# MCU_IMU.net
KiCad netlist of a schematic drawn in Altium Designer
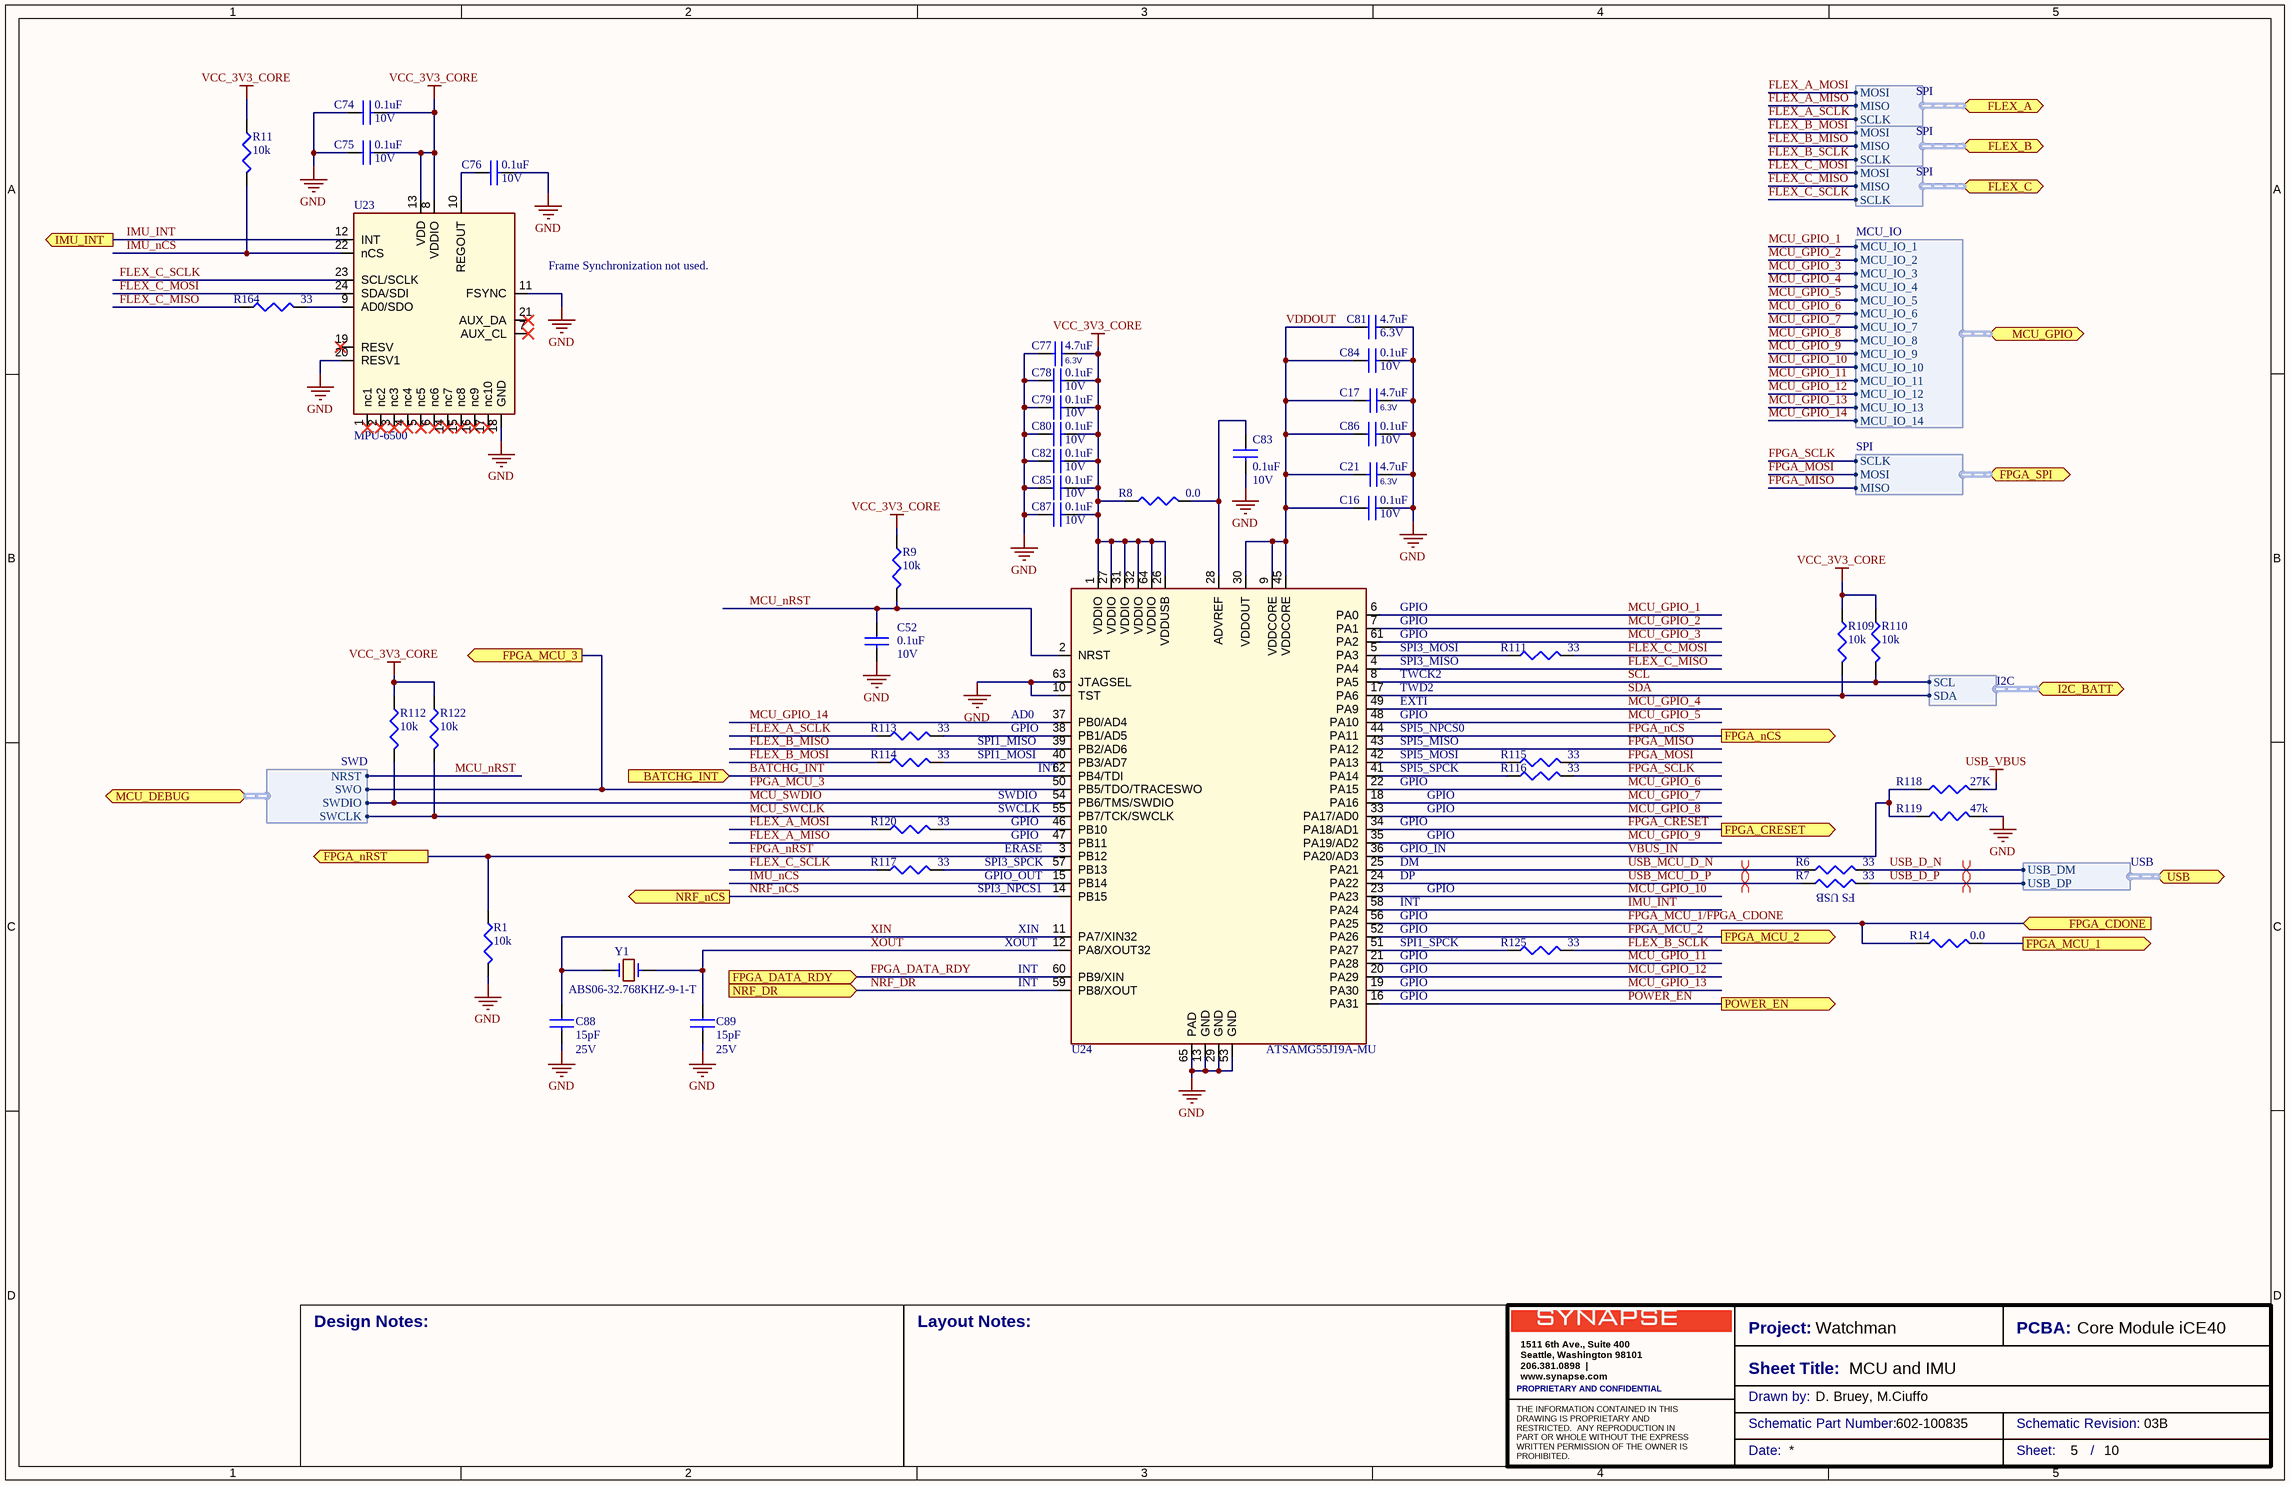
[diagram p0: MCU_IMU.SchDoc]

(export (version "E")
  (design (tool "Eeschema 10.0.6"))
  (components
    (comp (ref "C16")
      (value "0.1uF")
      (footprint "0201-IPCsm_33")
      (description "CAP CER 0.1UF 10V 10% X5R 0201")
      (fields
        (field (name "VOLTAGE") "10V")
        (field (name "MFG") "Samsung Electro-Mechanics America, Inc")
        (field (name "TOLERANCE") "10%")
      )
      (libsource (lib "SynapseLibrary") (part "CAP"))
    )
    (comp (ref "C17")
      (value "4.7uF")
      (footprint "0402-IPCsm_55")
      (description "CAP CER 4.7UF 6.3V 20% X5R 0402")
      (fields (field (name "VOLTAGE") "6.3V") (field (name "MFG") "MURATA") (field (name "TOLERANCE") "20%"))
      (libsource (lib "SynapseLibrary") (part "CAP"))
    )
    (comp (ref "C21")
      (value "4.7uF")
      (footprint "0402-IPCsm_55")
      (description "CAP CER 4.7UF 6.3V 20% X5R 0402")
      (fields (field (name "VOLTAGE") "6.3V") (field (name "MFG") "MURATA") (field (name "TOLERANCE") "20%"))
      (libsource (lib "SynapseLibrary") (part "CAP"))
    )
    (comp (ref "C52")
      (value "0.1uF")
      (footprint "0201-IPCsm_33")
      (description "CAP CER 0.1UF 10V 10% X5R 0201")
      (fields
        (field (name "VOLTAGE") "10V")
        (field (name "MFG") "Samsung Electro-Mechanics America, Inc")
        (field (name "TOLERANCE") "10%")
      )
      (libsource (lib "SynapseLibrary") (part "CAP"))
    )
    (comp (ref "C74")
      (value "0.1uF")
      (footprint "0201-IPCsm_33")
      (description "CAP CER 0.1UF 10V 10% X5R 0201")
      (fields
        (field (name "VOLTAGE") "10V")
        (field (name "MFG") "Samsung Electro-Mechanics America, Inc")
        (field (name "TOLERANCE") "10%")
      )
      (libsource (lib "SynapseLibrary") (part "CAP"))
    )
    (comp (ref "C75")
      (value "0.1uF")
      (footprint "0201-IPCsm_33")
      (description "CAP CER 0.1UF 10V 10% X5R 0201")
      (fields
        (field (name "VOLTAGE") "10V")
        (field (name "MFG") "Samsung Electro-Mechanics America, Inc")
        (field (name "TOLERANCE") "10%")
      )
      (libsource (lib "SynapseLibrary") (part "CAP"))
    )
    (comp (ref "C76")
      (value "0.1uF")
      (footprint "0201-IPCsm_33")
      (description "CAP CER 0.1UF 10V 10% X5R 0201")
      (fields
        (field (name "VOLTAGE") "10V")
        (field (name "MFG") "Samsung Electro-Mechanics America, Inc")
        (field (name "TOLERANCE") "10%")
      )
      (libsource (lib "SynapseLibrary") (part "CAP"))
    )
    (comp (ref "C77")
      (value "4.7uF")
      (footprint "0402-IPCsm_55")
      (description "CAP CER 4.7UF 6.3V 20% X5R 0402")
      (fields (field (name "VOLTAGE") "6.3V") (field (name "MFG") "MURATA") (field (name "TOLERANCE") "20%"))
      (libsource (lib "SynapseLibrary") (part "CAP"))
    )
    (comp (ref "C78")
      (value "0.1uF")
      (footprint "0201-IPCsm_33")
      (description "CAP CER 0.1UF 10V 10% X5R 0201")
      (fields
        (field (name "VOLTAGE") "10V")
        (field (name "MFG") "Samsung Electro-Mechanics America, Inc")
        (field (name "TOLERANCE") "10%")
      )
      (libsource (lib "SynapseLibrary") (part "CAP"))
    )
    (comp (ref "C79")
      (value "0.1uF")
      (footprint "0201-IPCsm_33")
      (description "CAP CER 0.1UF 10V 10% X5R 0201")
      (fields
        (field (name "VOLTAGE") "10V")
        (field (name "MFG") "Samsung Electro-Mechanics America, Inc")
        (field (name "TOLERANCE") "10%")
      )
      (libsource (lib "SynapseLibrary") (part "CAP"))
    )
    (comp (ref "C80")
      (value "0.1uF")
      (footprint "0201-IPCsm_33")
      (description "CAP CER 0.1UF 10V 10% X5R 0201")
      (fields
        (field (name "VOLTAGE") "10V")
        (field (name "MFG") "Samsung Electro-Mechanics America, Inc")
        (field (name "TOLERANCE") "10%")
      )
      (libsource (lib "SynapseLibrary") (part "CAP"))
    )
    (comp (ref "C81")
      (value "4.7uF")
      (footprint "0402-IPCsm_55")
      (description "CAP CER 4.7UF 6.3V 20% X5R 0402")
      (fields (field (name "VOLTAGE") "6.3V") (field (name "MFG") "MURATA") (field (name "TOLERANCE") "20%"))
      (libsource (lib "SynapseLibrary") (part "CAP"))
    )
    (comp (ref "C82")
      (value "0.1uF")
      (footprint "0201-IPCsm_33")
      (description "CAP CER 0.1UF 10V 10% X5R 0201")
      (fields
        (field (name "VOLTAGE") "10V")
        (field (name "MFG") "Samsung Electro-Mechanics America, Inc")
        (field (name "TOLERANCE") "10%")
      )
      (libsource (lib "SynapseLibrary") (part "CAP"))
    )
    (comp (ref "C83")
      (value "0.1uF")
      (footprint "0201-IPCsm_33")
      (description "CAP CER 0.1UF 10V 10% X5R 0201")
      (fields
        (field (name "VOLTAGE") "10V")
        (field (name "MFG") "Samsung Electro-Mechanics America, Inc")
        (field (name "TOLERANCE") "10%")
      )
      (libsource (lib "SynapseLibrary") (part "CAP"))
    )
    (comp (ref "C84")
      (value "0.1uF")
      (footprint "0201-IPCsm_33")
      (description "CAP CER 0.1UF 10V 10% X5R 0201")
      (fields
        (field (name "VOLTAGE") "10V")
        (field (name "MFG") "Samsung Electro-Mechanics America, Inc")
        (field (name "TOLERANCE") "10%")
      )
      (libsource (lib "SynapseLibrary") (part "CAP"))
    )
    (comp (ref "C85")
      (value "0.1uF")
      (footprint "0201-IPCsm_33")
      (description "CAP CER 0.1UF 10V 10% X5R 0201")
      (fields
        (field (name "VOLTAGE") "10V")
        (field (name "MFG") "Samsung Electro-Mechanics America, Inc")
        (field (name "TOLERANCE") "10%")
      )
      (libsource (lib "SynapseLibrary") (part "CAP"))
    )
    (comp (ref "C86")
      (value "0.1uF")
      (footprint "0201-IPCsm_33")
      (description "CAP CER 0.1UF 10V 10% X5R 0201")
      (fields
        (field (name "VOLTAGE") "10V")
        (field (name "MFG") "Samsung Electro-Mechanics America, Inc")
        (field (name "TOLERANCE") "10%")
      )
      (libsource (lib "SynapseLibrary") (part "CAP"))
    )
    (comp (ref "C87")
      (value "0.1uF")
      (footprint "0201-IPCsm_33")
      (description "CAP CER 0.1UF 10V 10% X5R 0201")
      (fields
        (field (name "VOLTAGE") "10V")
        (field (name "MFG") "Samsung Electro-Mechanics America, Inc")
        (field (name "TOLERANCE") "10%")
      )
      (libsource (lib "SynapseLibrary") (part "CAP"))
    )
    (comp (ref "C88")
      (value "15pF")
      (footprint "0201-IPCsm_33")
      (description "CAP CER 15PF 25V C0G 0201")
      (fields (field (name "VOLTAGE") "25V") (field (name "MFG") "Murata") (field (name "TOLERANCE") "5%"))
      (libsource (lib "SynapseLibrary") (part "CAP"))
    )
    (comp (ref "C89")
      (value "15pF")
      (footprint "0201-IPCsm_33")
      (description "CAP CER 15PF 25V C0G 0201")
      (fields (field (name "VOLTAGE") "25V") (field (name "MFG") "Murata") (field (name "TOLERANCE") "5%"))
      (libsource (lib "SynapseLibrary") (part "CAP"))
    )
    (comp (ref "R1")
      (value "10k")
      (footprint "0201-IPCsm_26")
      (description "RES 10K OHM 1/20W 1% 0201 SMD")
      (fields (field (name "TOLERANCE") "1.00%") (field (name "VOLTAGE") "50V"))
      (libsource (lib "SynapseLibrary") (part "RES"))
    )
    (comp (ref "R6")
      (value "33")
      (footprint "0201-IPCsm_26")
      (description "RES 33 OHM 1/20W 1% 0201 SMD")
      (fields (field (name "TOLERANCE") "1.00%") (field (name "VOLTAGE") "50V"))
      (libsource (lib "SynapseLibrary") (part "RES"))
    )
    (comp (ref "R7")
      (value "33")
      (footprint "0201-IPCsm_26")
      (description "RES 33 OHM 1/20W 1% 0201 SMD")
      (fields (field (name "TOLERANCE") "1.00%") (field (name "VOLTAGE") "50V"))
      (libsource (lib "SynapseLibrary") (part "RES"))
    )
    (comp (ref "R8")
      (value "0.0")
      (footprint "0201-IPCsm_26")
      (description "RES SMD 0.0OHM JUMPER 1/20W 0201")
      (fields (field (name "MFG") "Panasonic") (field (name "POWER") "0.05W"))
      (libsource (lib "SynapseLibrary") (part "RES"))
    )
    (comp (ref "R9")
      (value "10k")
      (footprint "0201-IPCsm_26")
      (description "RES 10K OHM 1/20W 1% 0201 SMD")
      (fields (field (name "TOLERANCE") "1.00%") (field (name "VOLTAGE") "50V"))
      (libsource (lib "SynapseLibrary") (part "RES"))
    )
    (comp (ref "R11")
      (value "10k")
      (footprint "0201-IPCsm_26")
      (description "RES 10K OHM 1/20W 1% 0201 SMD")
      (fields (field (name "TOLERANCE") "1.00%") (field (name "VOLTAGE") "50V"))
      (libsource (lib "SynapseLibrary") (part "RES"))
    )
    (comp (ref "R14")
      (value "0.0")
      (footprint "0201-IPCsm_26")
      (description "RES SMD 0.0OHM JUMPER 1/20W 0201")
      (fields (field (name "MFG") "Panasonic") (field (name "POWER") "0.05W"))
      (libsource (lib "SynapseLibrary") (part "RES"))
    )
    (comp (ref "R109")
      (value "10k")
      (footprint "0201-IPCsm_26")
      (description "RES 10K OHM 1/20W 1% 0201 SMD")
      (fields (field (name "TOLERANCE") "1.00%") (field (name "VOLTAGE") "50V"))
      (libsource (lib "SynapseLibrary") (part "RES"))
    )
    (comp (ref "R110")
      (value "10k")
      (footprint "0201-IPCsm_26")
      (description "RES 10K OHM 1/20W 1% 0201 SMD")
      (fields (field (name "TOLERANCE") "1.00%") (field (name "VOLTAGE") "50V"))
      (libsource (lib "SynapseLibrary") (part "RES"))
    )
    (comp (ref "R111")
      (value "33")
      (footprint "0201-IPCsm_26")
      (description "RES 33 OHM 1/20W 1% 0201 SMD")
      (fields (field (name "TOLERANCE") "1.00%") (field (name "VOLTAGE") "50V"))
      (libsource (lib "SynapseLibrary") (part "RES"))
    )
    (comp (ref "R112")
      (value "10k")
      (footprint "0201-IPCsm_26")
      (description "RES 10K OHM 1/20W 1% 0201 SMD")
      (fields (field (name "TOLERANCE") "1.00%") (field (name "VOLTAGE") "50V"))
      (libsource (lib "SynapseLibrary") (part "RES"))
    )
    (comp (ref "R113")
      (value "33")
      (footprint "0201-IPCsm_26")
      (description "RES 33 OHM 1/20W 1% 0201 SMD")
      (fields (field (name "TOLERANCE") "1.00%") (field (name "VOLTAGE") "50V"))
      (libsource (lib "SynapseLibrary") (part "RES"))
    )
    (comp (ref "R114")
      (value "33")
      (footprint "0201-IPCsm_26")
      (description "RES 33 OHM 1/20W 1% 0201 SMD")
      (fields (field (name "TOLERANCE") "1.00%") (field (name "VOLTAGE") "50V"))
      (libsource (lib "SynapseLibrary") (part "RES"))
    )
    (comp (ref "R115")
      (value "33")
      (footprint "0201-IPCsm_26")
      (description "RES 33 OHM 1/20W 1% 0201 SMD")
      (fields (field (name "TOLERANCE") "1.00%") (field (name "VOLTAGE") "50V"))
      (libsource (lib "SynapseLibrary") (part "RES"))
    )
    (comp (ref "R116")
      (value "33")
      (footprint "0201-IPCsm_26")
      (description "RES 33 OHM 1/20W 1% 0201 SMD")
      (fields (field (name "TOLERANCE") "1.00%") (field (name "VOLTAGE") "50V"))
      (libsource (lib "SynapseLibrary") (part "RES"))
    )
    (comp (ref "R117")
      (value "33")
      (footprint "0201-IPCsm_26")
      (description "RES 33 OHM 1/20W 1% 0201 SMD")
      (fields (field (name "TOLERANCE") "1.00%") (field (name "VOLTAGE") "50V"))
      (libsource (lib "SynapseLibrary") (part "RES"))
    )
    (comp (ref "R118")
      (value "27K")
      (footprint "0201-IPCsm_26")
      (description "RES 27K OHM 1/20W 1% 0201 SMD")
      (fields (field (name "TOLERANCE") "1.00%") (field (name "VOLTAGE") "15V"))
      (libsource (lib "SynapseLibrary") (part "RES"))
    )
    (comp (ref "R119")
      (value "47k")
      (footprint "0201-IPCsm_26")
      (description "RES 47K OHM 1/20W 5% 0201 SMD")
      (fields (field (name "TOLERANCE") "5.00%") (field (name "VOLTAGE") "50V"))
      (libsource (lib "SynapseLibrary") (part "RES"))
    )
    (comp (ref "R120")
      (value "33")
      (footprint "0201-IPCsm_26")
      (description "RES 33 OHM 1/20W 1% 0201 SMD")
      (fields (field (name "TOLERANCE") "1.00%") (field (name "VOLTAGE") "50V"))
      (libsource (lib "SynapseLibrary") (part "RES"))
    )
    (comp (ref "R122")
      (value "10k")
      (footprint "0201-IPCsm_26")
      (description "RES 10K OHM 1/20W 1% 0201 SMD")
      (fields (field (name "TOLERANCE") "1.00%") (field (name "VOLTAGE") "50V"))
      (libsource (lib "SynapseLibrary") (part "RES"))
    )
    (comp (ref "R125")
      (value "33")
      (footprint "0201-IPCsm_26")
      (description "RES 33 OHM 1/20W 1% 0201 SMD")
      (fields (field (name "TOLERANCE") "1.00%") (field (name "VOLTAGE") "50V"))
      (libsource (lib "SynapseLibrary") (part "RES"))
    )
    (comp (ref "R164")
      (value "33")
      (footprint "0201-IPCsm_26")
      (description "RES 33 OHM 1/20W 1% 0201 SMD")
      (fields (field (name "TOLERANCE") "1.00%") (field (name "VOLTAGE") "50V"))
      (libsource (lib "SynapseLibrary") (part "RES"))
    )
    (comp (ref "U23")
      (value "MPU-6500")
      (footprint "QFN24_mpu-6500_3x3")
      (description "6-axis Gyroscope/Accelerometer")
      (fields (field (name "MFG") "InvenSense"))
      (libsource (lib "SynapseLibrary") (part "MPU-6500a"))
    )
    (comp (ref "U24")
      (value "ATSAMG55J19A-MU")
      (footprint "qfn64_atsamg55j19a_no_vias")
      (description "IC MCU 32BIT 512KB FLASH 64VQFN")
      (fields (field (name "MFG") "Atmel") (field (name "VOLTAGE") "1.62V~3.6V"))
      (libsource (lib "SynapseLibrary") (part "ATSAMG55J19A-MU"))
    )
    (comp (ref "Y1")
      (value "ABS06-32.768KHZ-9-1-T")
      (footprint "xtal_abs06")
      (description "CRYSTAL 32.768 KHZ 9PF SMD")
      (fields (field (name "MFG") "Abracon") (field (name "TOLERANCE") "+/- 10ppm"))
      (libsource (lib "SynapseLibrary") (part "XTAL_32K"))
    )
  )
  (nets
    (net (code "6") (name "/BATCHG_INT") (class "Default")
      (node (ref "U24") (pin "62") (pinfunction "PB4/TDI_62") (pintype "passive"))
    )
    (net (code "7") (name "/FLEX_A_MISO") (class "Default")
      (node (ref "U24") (pin "47") (pinfunction "PB11_47") (pintype "passive"))
    )
    (net (code "8") (name "/FLEX_A_MOSI") (class "Default")
      (node (ref "R120") (pin "1") (pinfunction "1_1") (pintype "passive"))
    )
    (net (code "9") (name "/FLEX_A_SCLK") (class "Default")
      (node (ref "R113") (pin "1") (pinfunction "1_1") (pintype "passive"))
    )
    (net (code "10") (name "/FLEX_B_MISO") (class "Default")
      (node (ref "U24") (pin "39") (pinfunction "PB2/AD6_39") (pintype "passive"))
    )
    (net (code "11") (name "/FLEX_B_MOSI") (class "Default")
      (node (ref "R114") (pin "1") (pinfunction "1_1") (pintype "passive"))
    )
    (net (code "12") (name "/FLEX_B_SCLK") (class "Default")
      (node (ref "R125") (pin "2") (pinfunction "2_2") (pintype "passive"))
    )
    (net (code "13") (name "/FLEX_C_MISO") (class "Default")
      (node (ref "R164") (pin "1") (pinfunction "1_1") (pintype "passive"))
      (node (ref "U24") (pin "4") (pinfunction "PA4_4") (pintype "passive"))
    )
    (net (code "14") (name "/FLEX_C_MOSI") (class "Default")
      (node (ref "R111") (pin "2") (pinfunction "2_2") (pintype "passive"))
      (node (ref "U23") (pin "24") (pinfunction "SDA/SDI_24") (pintype "passive"))
    )
    (net (code "15") (name "/FLEX_C_SCLK") (class "Default")
      (node (ref "R117") (pin "1") (pinfunction "1_1") (pintype "passive"))
      (node (ref "U23") (pin "23") (pinfunction "SCL/SCLK_23") (pintype "passive"))
    )
    (net (code "16") (name "/FPGA_CRESET") (class "Default")
      (node (ref "U24") (pin "34") (pinfunction "PA18/AD1_34") (pintype "passive"))
    )
    (net (code "17") (name "/FPGA_DATA_RDY") (class "Default")
      (node (ref "U24") (pin "60") (pinfunction "PB9/XIN_60") (pintype "passive"))
    )
    (net (code "18") (name "/FPGA_MCU_1") (class "Default")
      (node (ref "R14") (pin "1") (pinfunction "1_1") (pintype "passive"))
    )
    (net (code "19") (name "/FPGA_MCU_1{slash}FPGA_CDONE") (class "Default")
      (node (ref "R14") (pin "2") (pinfunction "2_2") (pintype "passive"))
      (node (ref "U24") (pin "56") (pinfunction "PA25_56") (pintype "passive"))
    )
    (net (code "20") (name "/FPGA_MCU_2") (class "Default")
      (node (ref "U24") (pin "52") (pinfunction "PA26_52") (pintype "passive"))
    )
    (net (code "21") (name "/FPGA_MCU_3") (class "Default")
      (node (ref "U24") (pin "50") (pinfunction "PB5/TDO/TRACESWO_50") (pintype "passive"))
    )
    (net (code "22") (name "/FPGA_MISO") (class "Default")
      (node (ref "U24") (pin "43") (pinfunction "PA12_43") (pintype "passive"))
    )
    (net (code "23") (name "/FPGA_MOSI") (class "Default")
      (node (ref "R115") (pin "2") (pinfunction "2_2") (pintype "passive"))
    )
    (net (code "24") (name "/FPGA_SCLK") (class "Default")
      (node (ref "R116") (pin "2") (pinfunction "2_2") (pintype "passive"))
    )
    (net (code "25") (name "/FPGA_nCS") (class "Default")
      (node (ref "U24") (pin "44") (pinfunction "PA11_44") (pintype "passive"))
    )
    (net (code "26") (name "/FPGA_nRST") (class "Default")
      (node (ref "R1") (pin "1") (pinfunction "1_1") (pintype "passive"))
      (node (ref "U24") (pin "3") (pinfunction "PB12_3") (pintype "passive"))
    )
    (net (code "27") (name "/IMU_INT") (class "Default")
      (node (ref "U23") (pin "12") (pinfunction "INT_12") (pintype "passive"))
      (node (ref "U24") (pin "58") (pinfunction "PA24_58") (pintype "passive"))
    )
    (net (code "28") (name "/IMU_nCS") (class "Default")
      (node (ref "R11") (pin "2") (pinfunction "2_2") (pintype "passive"))
      (node (ref "U23") (pin "22") (pinfunction "nCS_22") (pintype "passive"))
      (node (ref "U24") (pin "15") (pinfunction "PB14_15") (pintype "passive"))
    )
    (net (code "29") (name "/MCU_GPIO_1") (class "Default")
      (node (ref "U24") (pin "6") (pinfunction "PA0_6") (pintype "passive"))
    )
    (net (code "30") (name "/MCU_GPIO_2") (class "Default")
      (node (ref "U24") (pin "7") (pinfunction "PA1_7") (pintype "passive"))
    )
    (net (code "31") (name "/MCU_GPIO_3") (class "Default")
      (node (ref "U24") (pin "61") (pinfunction "PA2_61") (pintype "passive"))
    )
    (net (code "32") (name "/MCU_GPIO_4") (class "Default")
      (node (ref "U24") (pin "49") (pinfunction "PA9_49") (pintype "passive"))
    )
    (net (code "33") (name "/MCU_GPIO_5") (class "Default")
      (node (ref "U24") (pin "48") (pinfunction "PA10_48") (pintype "passive"))
    )
    (net (code "34") (name "/MCU_GPIO_6") (class "Default")
      (node (ref "U24") (pin "22") (pinfunction "PA15_22") (pintype "passive"))
    )
    (net (code "35") (name "/MCU_GPIO_7") (class "Default")
      (node (ref "U24") (pin "18") (pinfunction "PA16_18") (pintype "passive"))
    )
    (net (code "36") (name "/MCU_GPIO_8") (class "Default")
      (node (ref "U24") (pin "33") (pinfunction "PA17/AD0_33") (pintype "passive"))
    )
    (net (code "37") (name "/MCU_GPIO_9") (class "Default")
      (node (ref "U24") (pin "35") (pinfunction "PA19/AD2_35") (pintype "passive"))
    )
    (net (code "38") (name "/MCU_GPIO_10") (class "Default")
      (node (ref "U24") (pin "23") (pinfunction "PA23_23") (pintype "passive"))
    )
    (net (code "39") (name "/MCU_GPIO_11") (class "Default")
      (node (ref "U24") (pin "21") (pinfunction "PA28_21") (pintype "passive"))
    )
    (net (code "40") (name "/MCU_GPIO_12") (class "Default")
      (node (ref "U24") (pin "20") (pinfunction "PA29_20") (pintype "passive"))
    )
    (net (code "41") (name "/MCU_GPIO_13") (class "Default")
      (node (ref "U24") (pin "19") (pinfunction "PA30_19") (pintype "passive"))
    )
    (net (code "42") (name "/MCU_GPIO_14") (class "Default")
      (node (ref "U24") (pin "37") (pinfunction "PB0/AD4_37") (pintype "passive"))
    )
    (net (code "43") (name "/MCU_SWCLK") (class "Default")
      (node (ref "R122") (pin "2") (pinfunction "2_2") (pintype "passive"))
      (node (ref "U24") (pin "55") (pinfunction "PB7/TCK/SWCLK_55") (pintype "passive"))
    )
    (net (code "44") (name "/MCU_SWDIO") (class "Default")
      (node (ref "R112") (pin "2") (pinfunction "2_2") (pintype "passive"))
      (node (ref "U24") (pin "54") (pinfunction "PB6/TMS/SWDIO_54") (pintype "passive"))
    )
    (net (code "45") (name "/MCU_nRST") (class "Default")
      (node (ref "C52") (pin "1") (pinfunction "1_1") (pintype "passive"))
      (node (ref "R9") (pin "2") (pinfunction "2_2") (pintype "passive"))
      (node (ref "U24") (pin "2") (pinfunction "NRST_2") (pintype "passive"))
    )
    (net (code "46") (name "/NRF_DR") (class "Default")
      (node (ref "U24") (pin "59") (pinfunction "PB8/XOUT_59") (pintype "passive"))
    )
    (net (code "47") (name "/NRF_nCS") (class "Default")
      (node (ref "U24") (pin "14") (pinfunction "PB15_14") (pintype "passive"))
    )
    (net (code "48") (name "/POWER_EN") (class "Default")
      (node (ref "U24") (pin "16") (pinfunction "PA31_16") (pintype "passive"))
    )
    (net (code "49") (name "/SCL") (class "Default")
      (node (ref "R110") (pin "2") (pinfunction "2_2") (pintype "passive"))
      (node (ref "U24") (pin "8") (pinfunction "PA5_8") (pintype "passive"))
    )
    (net (code "50") (name "/SDA") (class "Default")
      (node (ref "R109") (pin "2") (pinfunction "2_2") (pintype "passive"))
      (node (ref "U24") (pin "17") (pinfunction "PA6_17") (pintype "passive"))
    )
    (net (code "51") (name "/USB_D_N") (class "Default")
      (node (ref "R6") (pin "2") (pinfunction "2_2") (pintype "passive"))
    )
    (net (code "52") (name "/USB_D_P") (class "Default")
      (node (ref "R7") (pin "2") (pinfunction "2_2") (pintype "passive"))
    )
    (net (code "53") (name "/USB_MCU_D_N") (class "Default")
      (node (ref "R6") (pin "1") (pinfunction "1_1") (pintype "passive"))
      (node (ref "U24") (pin "25") (pinfunction "PA21_25") (pintype "passive"))
    )
    (net (code "54") (name "/USB_MCU_D_P") (class "Default")
      (node (ref "R7") (pin "1") (pinfunction "1_1") (pintype "passive"))
      (node (ref "U24") (pin "24") (pinfunction "PA22_24") (pintype "passive"))
    )
    (net (code "55") (name "/VBUS_IN") (class "Default")
      (node (ref "R118") (pin "1") (pinfunction "1_1") (pintype "passive"))
      (node (ref "R119") (pin "1") (pinfunction "1_1") (pintype "passive"))
      (node (ref "U24") (pin "36") (pinfunction "PA20/AD3_36") (pintype "passive"))
    )
    (net (code "56") (name "/VDDOUT") (class "Default")
      (node (ref "C16") (pin "1") (pinfunction "1_1") (pintype "passive"))
      (node (ref "C17") (pin "2") (pinfunction "2_2") (pintype "passive"))
      (node (ref "C21") (pin "2") (pinfunction "2_2") (pintype "passive"))
      (node (ref "C81") (pin "1") (pinfunction "1_1") (pintype "passive"))
      (node (ref "C84") (pin "1") (pinfunction "1_1") (pintype "passive"))
      (node (ref "C86") (pin "1") (pinfunction "1_1") (pintype "passive"))
      (node (ref "U24") (pin "30") (pinfunction "VDDOUT_30") (pintype "passive"))
      (node (ref "U24") (pin "45") (pinfunction "VDDCORE_45") (pintype "passive"))
      (node (ref "U24") (pin "9") (pinfunction "VDDCORE_9") (pintype "passive"))
    )
    (net (code "57") (name "/XIN") (class "Default")
      (node (ref "C88") (pin "1") (pinfunction "1_1") (pintype "passive"))
      (node (ref "U24") (pin "11") (pinfunction "PA7/XIN32_11") (pintype "passive"))
      (node (ref "Y1") (pin "1") (pinfunction "1_1") (pintype "passive"))
    )
    (net (code "58") (name "/XOUT") (class "Default")
      (node (ref "C89") (pin "1") (pinfunction "1_1") (pintype "passive"))
      (node (ref "U24") (pin "12") (pinfunction "PA8/XOUT32_12") (pintype "passive"))
      (node (ref "Y1") (pin "2") (pinfunction "2_2") (pintype "passive"))
    )
    (net (code "64") (name "GND") (class "Default")
      (node (ref "C16") (pin "2") (pinfunction "2_2") (pintype "passive"))
      (node (ref "C17") (pin "1") (pinfunction "1_1") (pintype "passive"))
      (node (ref "C21") (pin "1") (pinfunction "1_1") (pintype "passive"))
      (node (ref "C52") (pin "2") (pinfunction "2_2") (pintype "passive"))
      (node (ref "C74") (pin "1") (pinfunction "1_1") (pintype "passive"))
      (node (ref "C75") (pin "1") (pinfunction "1_1") (pintype "passive"))
      (node (ref "C76") (pin "2") (pinfunction "2_2") (pintype "passive"))
      (node (ref "C77") (pin "2") (pinfunction "2_2") (pintype "passive"))
      (node (ref "C78") (pin "1") (pinfunction "1_1") (pintype "passive"))
      (node (ref "C79") (pin "1") (pinfunction "1_1") (pintype "passive"))
      (node (ref "C80") (pin "1") (pinfunction "1_1") (pintype "passive"))
      (node (ref "C81") (pin "2") (pinfunction "2_2") (pintype "passive"))
      (node (ref "C82") (pin "1") (pinfunction "1_1") (pintype "passive"))
      (node (ref "C83") (pin "2") (pinfunction "2_2") (pintype "passive"))
      (node (ref "C84") (pin "2") (pinfunction "2_2") (pintype "passive"))
      (node (ref "C85") (pin "1") (pinfunction "1_1") (pintype "passive"))
      (node (ref "C86") (pin "2") (pinfunction "2_2") (pintype "passive"))
      (node (ref "C87") (pin "1") (pinfunction "1_1") (pintype "passive"))
      (node (ref "C88") (pin "2") (pinfunction "2_2") (pintype "passive"))
      (node (ref "C89") (pin "2") (pinfunction "2_2") (pintype "passive"))
      (node (ref "R1") (pin "2") (pinfunction "2_2") (pintype "passive"))
      (node (ref "R119") (pin "2") (pinfunction "2_2") (pintype "passive"))
      (node (ref "U23") (pin "11") (pinfunction "FSYNC_11") (pintype "passive"))
      (node (ref "U23") (pin "18") (pinfunction "GND_18") (pintype "passive"))
      (node (ref "U23") (pin "20") (pinfunction "RESV1_20") (pintype "passive"))
      (node (ref "U24") (pin "10") (pinfunction "TST_10") (pintype "passive"))
      (node (ref "U24") (pin "13") (pinfunction "GND_13") (pintype "passive"))
      (node (ref "U24") (pin "29") (pinfunction "GND_29") (pintype "passive"))
      (node (ref "U24") (pin "53") (pinfunction "GND_53") (pintype "passive"))
      (node (ref "U24") (pin "63") (pinfunction "JTAGSEL_63") (pintype "passive"))
      (node (ref "U24") (pin "65") (pinfunction "PAD_65") (pintype "passive"))
    )
    (net (code "65") (name "Net-(U23-AD0{slash}SDO)") (class "Default")
      (node (ref "R164") (pin "2") (pinfunction "2_2") (pintype "passive"))
      (node (ref "U23") (pin "9") (pinfunction "AD0/SDO_9") (pintype "passive"))
    )
    (net (code "66") (name "Net-(U23-REGOUT)") (class "Default")
      (node (ref "C76") (pin "1") (pinfunction "1_1") (pintype "passive"))
      (node (ref "U23") (pin "10") (pinfunction "REGOUT_10") (pintype "passive"))
    )
    (net (code "67") (name "Net-(U24-ADVREF)") (class "Default")
      (node (ref "C83") (pin "1") (pinfunction "1_1") (pintype "passive"))
      (node (ref "R8") (pin "2") (pinfunction "2_2") (pintype "passive"))
      (node (ref "U24") (pin "28") (pinfunction "ADVREF_28") (pintype "passive"))
    )
    (net (code "68") (name "Net-(U24-PA3)") (class "Default")
      (node (ref "R111") (pin "1") (pinfunction "1_1") (pintype "passive"))
      (node (ref "U24") (pin "5") (pinfunction "PA3_5") (pintype "passive"))
    )
    (net (code "69") (name "Net-(U24-PA13)") (class "Default")
      (node (ref "R115") (pin "1") (pinfunction "1_1") (pintype "passive"))
      (node (ref "U24") (pin "42") (pinfunction "PA13_42") (pintype "passive"))
    )
    (net (code "70") (name "Net-(U24-PA14)") (class "Default")
      (node (ref "R116") (pin "1") (pinfunction "1_1") (pintype "passive"))
      (node (ref "U24") (pin "41") (pinfunction "PA14_41") (pintype "passive"))
    )
    (net (code "71") (name "Net-(U24-PA27)") (class "Default")
      (node (ref "R125") (pin "1") (pinfunction "1_1") (pintype "passive"))
      (node (ref "U24") (pin "51") (pinfunction "PA27_51") (pintype "passive"))
    )
    (net (code "72") (name "Net-(U24-PB1{slash}AD5)") (class "Default")
      (node (ref "R113") (pin "2") (pinfunction "2_2") (pintype "passive"))
      (node (ref "U24") (pin "38") (pinfunction "PB1/AD5_38") (pintype "passive"))
    )
    (net (code "73") (name "Net-(U24-PB3{slash}AD7)") (class "Default")
      (node (ref "R114") (pin "2") (pinfunction "2_2") (pintype "passive"))
      (node (ref "U24") (pin "40") (pinfunction "PB3/AD7_40") (pintype "passive"))
    )
    (net (code "74") (name "Net-(U24-PB10)") (class "Default")
      (node (ref "R120") (pin "2") (pinfunction "2_2") (pintype "passive"))
      (node (ref "U24") (pin "46") (pinfunction "PB10_46") (pintype "passive"))
    )
    (net (code "75") (name "Net-(U24-PB13)") (class "Default")
      (node (ref "R117") (pin "2") (pinfunction "2_2") (pintype "passive"))
      (node (ref "U24") (pin "57") (pinfunction "PB13_57") (pintype "passive"))
    )
    (net (code "76") (name "USB_VBUS") (class "Default")
      (node (ref "R118") (pin "2") (pinfunction "2_2") (pintype "passive"))
    )
    (net (code "77") (name "VCC_3V3_CORE") (class "Default")
      (node (ref "C74") (pin "2") (pinfunction "2_2") (pintype "passive"))
      (node (ref "C75") (pin "2") (pinfunction "2_2") (pintype "passive"))
      (node (ref "C77") (pin "1") (pinfunction "1_1") (pintype "passive"))
      (node (ref "C78") (pin "2") (pinfunction "2_2") (pintype "passive"))
      (node (ref "C79") (pin "2") (pinfunction "2_2") (pintype "passive"))
      (node (ref "C80") (pin "2") (pinfunction "2_2") (pintype "passive"))
      (node (ref "C82") (pin "2") (pinfunction "2_2") (pintype "passive"))
      (node (ref "C85") (pin "2") (pinfunction "2_2") (pintype "passive"))
      (node (ref "C87") (pin "2") (pinfunction "2_2") (pintype "passive"))
      (node (ref "R109") (pin "1") (pinfunction "1_1") (pintype "passive"))
      (node (ref "R11") (pin "1") (pinfunction "1_1") (pintype "passive"))
      (node (ref "R110") (pin "1") (pinfunction "1_1") (pintype "passive"))
      (node (ref "R112") (pin "1") (pinfunction "1_1") (pintype "passive"))
      (node (ref "R122") (pin "1") (pinfunction "1_1") (pintype "passive"))
      (node (ref "R8") (pin "1") (pinfunction "1_1") (pintype "passive"))
      (node (ref "R9") (pin "1") (pinfunction "1_1") (pintype "passive"))
      (node (ref "U23") (pin "13") (pinfunction "VDD_13") (pintype "passive"))
      (node (ref "U23") (pin "8") (pinfunction "VDDIO_8") (pintype "passive"))
      (node (ref "U24") (pin "1") (pinfunction "VDDIO_1") (pintype "passive"))
      (node (ref "U24") (pin "26") (pinfunction "VDDUSB_26") (pintype "passive"))
      (node (ref "U24") (pin "27") (pinfunction "VDDIO_27") (pintype "passive"))
      (node (ref "U24") (pin "31") (pinfunction "VDDIO_31") (pintype "passive"))
      (node (ref "U24") (pin "32") (pinfunction "VDDIO_32") (pintype "passive"))
      (node (ref "U24") (pin "64") (pinfunction "VDDIO_64") (pintype "passive"))
    )
    (net (code "78") (name "unconnected-(U23-AUX_CL-Pad7)") (class "Default")
      (node (ref "U23") (pin "7") (pinfunction "AUX_CL_7") (pintype "passive+no_connect"))
    )
    (net (code "79") (name "unconnected-(U23-AUX_DA-Pad21)") (class "Default")
      (node (ref "U23") (pin "21") (pinfunction "AUX_DA_21") (pintype "passive+no_connect"))
    )
    (net (code "80") (name "unconnected-(U23-RESV-Pad19)") (class "Default")
      (node (ref "U23") (pin "19") (pinfunction "RESV_19") (pintype "passive+no_connect"))
    )
    (net (code "81") (name "unconnected-(U23-nc1-Pad1)") (class "Default")
      (node (ref "U23") (pin "1") (pinfunction "nc1_1") (pintype "passive+no_connect"))
    )
    (net (code "82") (name "unconnected-(U23-nc2-Pad2)") (class "Default")
      (node (ref "U23") (pin "2") (pinfunction "nc2_2") (pintype "passive+no_connect"))
    )
    (net (code "83") (name "unconnected-(U23-nc3-Pad3)") (class "Default")
      (node (ref "U23") (pin "3") (pinfunction "nc3_3") (pintype "passive+no_connect"))
    )
    (net (code "84") (name "unconnected-(U23-nc4-Pad4)") (class "Default")
      (node (ref "U23") (pin "4") (pinfunction "nc4_4") (pintype "passive+no_connect"))
    )
    (net (code "85") (name "unconnected-(U23-nc5-Pad5)") (class "Default")
      (node (ref "U23") (pin "5") (pinfunction "nc5_5") (pintype "passive+no_connect"))
    )
    (net (code "86") (name "unconnected-(U23-nc6-Pad6)") (class "Default")
      (node (ref "U23") (pin "6") (pinfunction "nc6_6") (pintype "passive+no_connect"))
    )
    (net (code "87") (name "unconnected-(U23-nc7-Pad14)") (class "Default")
      (node (ref "U23") (pin "14") (pinfunction "nc7_14") (pintype "passive+no_connect"))
    )
    (net (code "88") (name "unconnected-(U23-nc8-Pad15)") (class "Default")
      (node (ref "U23") (pin "15") (pinfunction "nc8_15") (pintype "passive+no_connect"))
    )
    (net (code "89") (name "unconnected-(U23-nc9-Pad16)") (class "Default")
      (node (ref "U23") (pin "16") (pinfunction "nc9_16") (pintype "passive+no_connect"))
    )
    (net (code "90") (name "unconnected-(U23-nc10-Pad17)") (class "Default")
      (node (ref "U23") (pin "17") (pinfunction "nc10_17") (pintype "passive+no_connect"))
    )
  )
)
